# AnalogPair.net
KiCad netlist of a schematic drawn in EAGLE
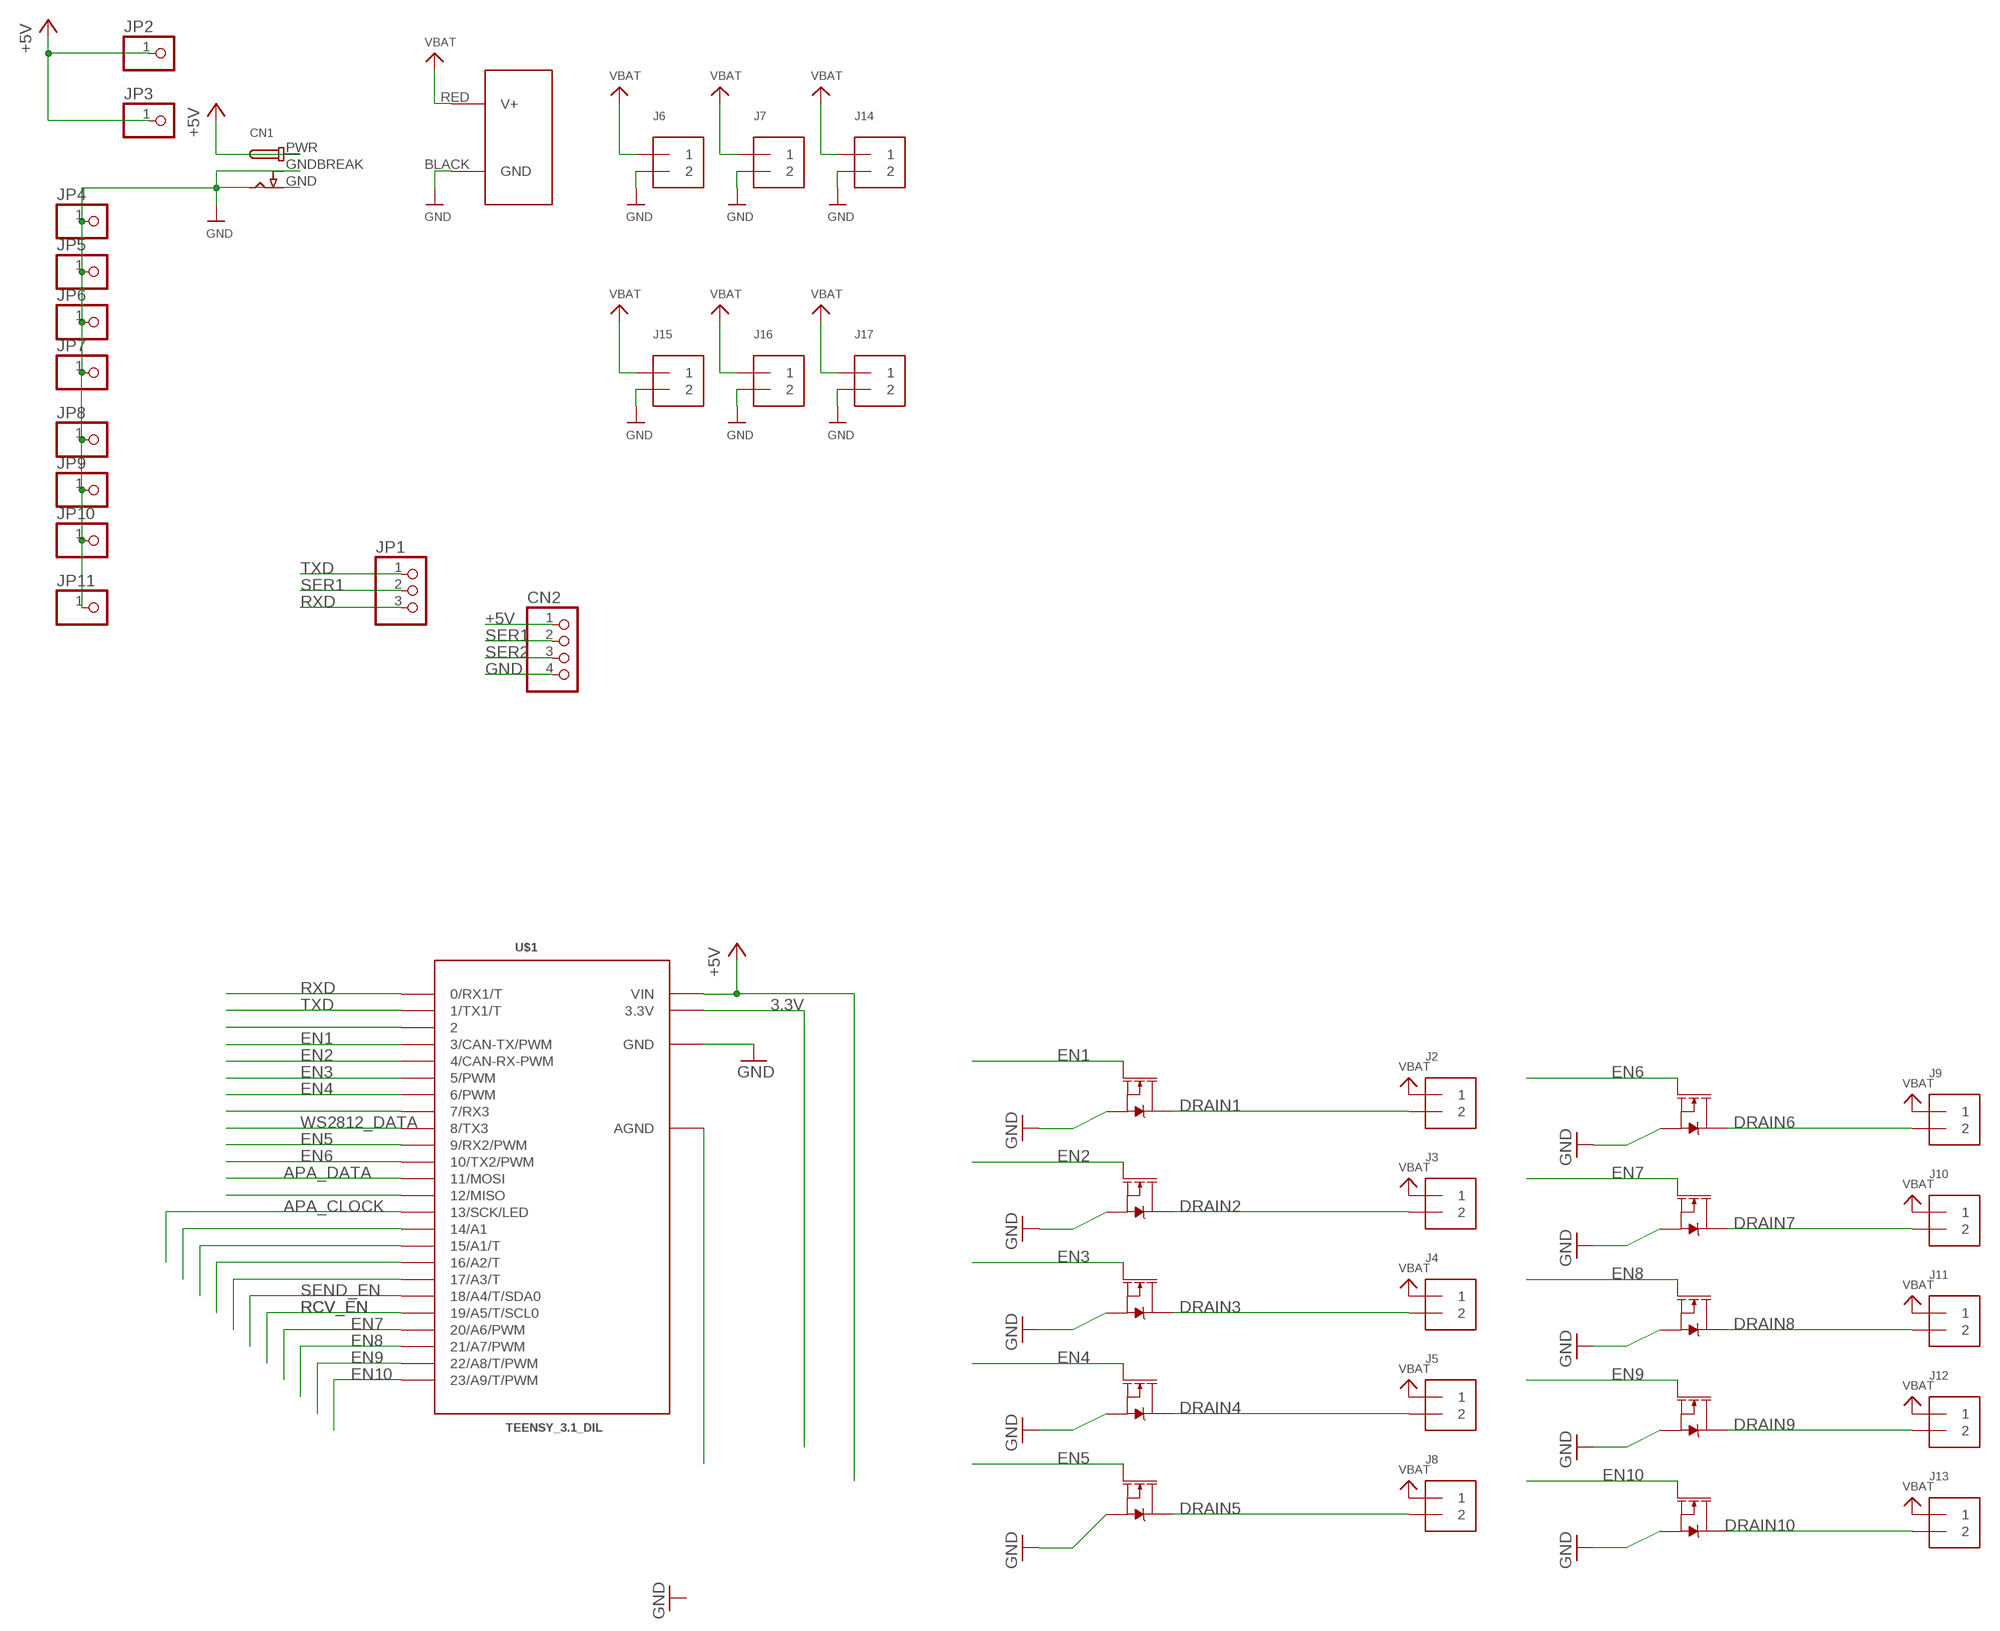
[diagram p0: schematic, sheet 1]

(export (version "E")
  (design (tool "Eeschema 10.0.6"))
  (components
    (comp (ref "CN1")
      (value "DCBARRELPTH")
      (footprint "eagle-import:DCJACK_2MM_PTH")
      (libsource (lib "eagle-import") (part "DCBARRELPTH"))
    )
    (comp (ref "CN2")
      (value "HEADER-1X4")
      (footprint "eagle-import:1X04_OVAL")
      (libsource (lib "eagle-import") (part "HEADER-1X4"))
    )
    (comp (ref "J1")
      (value "POWERPOLE_POWER25A")
      (footprint "eagle-import:POWERPOLE_PAIR_25A")
      (libsource (lib "eagle-import") (part "POWERPOLE_POWER25A"))
    )
    (comp (ref "J2")
      (value "TERMBLOCK_1X2")
      (footprint "eagle-import:TERMBLOCK_1X2-3.5MM")
      (libsource (lib "eagle-import") (part "TERMBLOCK_1X2"))
    )
    (comp (ref "J3")
      (value "TERMBLOCK_1X2")
      (footprint "eagle-import:TERMBLOCK_1X2-3.5MM")
      (libsource (lib "eagle-import") (part "TERMBLOCK_1X2"))
    )
    (comp (ref "J4")
      (value "TERMBLOCK_1X2")
      (footprint "eagle-import:TERMBLOCK_1X2-3.5MM")
      (libsource (lib "eagle-import") (part "TERMBLOCK_1X2"))
    )
    (comp (ref "J5")
      (value "TERMBLOCK_1X2")
      (footprint "eagle-import:TERMBLOCK_1X2-3.5MM")
      (libsource (lib "eagle-import") (part "TERMBLOCK_1X2"))
    )
    (comp (ref "J6")
      (value "TERMBLOCK_1X2")
      (footprint "eagle-import:TERMBLOCK_1X2-3.5MM")
      (libsource (lib "eagle-import") (part "TERMBLOCK_1X2"))
    )
    (comp (ref "J7")
      (value "TERMBLOCK_1X2")
      (footprint "eagle-import:TERMBLOCK_1X2-3.5MM")
      (libsource (lib "eagle-import") (part "TERMBLOCK_1X2"))
    )
    (comp (ref "J8")
      (value "TERMBLOCK_1X2")
      (footprint "eagle-import:TERMBLOCK_1X2-3.5MM")
      (libsource (lib "eagle-import") (part "TERMBLOCK_1X2"))
    )
    (comp (ref "J9")
      (value "TERMBLOCK_1X2")
      (footprint "eagle-import:TERMBLOCK_1X2-3.5MM")
      (libsource (lib "eagle-import") (part "TERMBLOCK_1X2"))
    )
    (comp (ref "J10")
      (value "TERMBLOCK_1X2")
      (footprint "eagle-import:TERMBLOCK_1X2-3.5MM")
      (libsource (lib "eagle-import") (part "TERMBLOCK_1X2"))
    )
    (comp (ref "J11")
      (value "TERMBLOCK_1X2")
      (footprint "eagle-import:TERMBLOCK_1X2-3.5MM")
      (libsource (lib "eagle-import") (part "TERMBLOCK_1X2"))
    )
    (comp (ref "J12")
      (value "TERMBLOCK_1X2")
      (footprint "eagle-import:TERMBLOCK_1X2-3.5MM")
      (libsource (lib "eagle-import") (part "TERMBLOCK_1X2"))
    )
    (comp (ref "J13")
      (value "TERMBLOCK_1X2")
      (footprint "eagle-import:TERMBLOCK_1X2-3.5MM")
      (libsource (lib "eagle-import") (part "TERMBLOCK_1X2"))
    )
    (comp (ref "J14")
      (value "TERMBLOCK_1X2")
      (footprint "eagle-import:TERMBLOCK_1X2-3.5MM")
      (libsource (lib "eagle-import") (part "TERMBLOCK_1X2"))
    )
    (comp (ref "J15")
      (value "TERMBLOCK_1X2")
      (footprint "eagle-import:TERMBLOCK_1X2-3.5MM")
      (libsource (lib "eagle-import") (part "TERMBLOCK_1X2"))
    )
    (comp (ref "J16")
      (value "TERMBLOCK_1X2")
      (footprint "eagle-import:TERMBLOCK_1X2-3.5MM")
      (libsource (lib "eagle-import") (part "TERMBLOCK_1X2"))
    )
    (comp (ref "J17")
      (value "TERMBLOCK_1X2")
      (footprint "eagle-import:TERMBLOCK_1X2-3.5MM")
      (libsource (lib "eagle-import") (part "TERMBLOCK_1X2"))
    )
    (comp (ref "JP1")
      (value "PINHD-1X3")
      (footprint "eagle-import:1X03")
      (libsource (lib "eagle-import") (part "PINHD-1X3"))
    )
    (comp (ref "JP2")
      (value "PINHD-1X1")
      (footprint "eagle-import:1X01")
      (libsource (lib "eagle-import") (part "PINHD-1X1"))
    )
    (comp (ref "JP3")
      (value "PINHD-1X1")
      (footprint "eagle-import:1X01")
      (libsource (lib "eagle-import") (part "PINHD-1X1"))
    )
    (comp (ref "JP4")
      (value "PINHD-1X1")
      (footprint "eagle-import:1X01")
      (libsource (lib "eagle-import") (part "PINHD-1X1"))
    )
    (comp (ref "JP5")
      (value "PINHD-1X1")
      (footprint "eagle-import:1X01")
      (libsource (lib "eagle-import") (part "PINHD-1X1"))
    )
    (comp (ref "JP6")
      (value "PINHD-1X1")
      (footprint "eagle-import:1X01")
      (libsource (lib "eagle-import") (part "PINHD-1X1"))
    )
    (comp (ref "JP7")
      (value "PINHD-1X1")
      (footprint "eagle-import:1X01")
      (libsource (lib "eagle-import") (part "PINHD-1X1"))
    )
    (comp (ref "JP8")
      (value "PINHD-1X1")
      (footprint "eagle-import:1X01")
      (libsource (lib "eagle-import") (part "PINHD-1X1"))
    )
    (comp (ref "JP9")
      (value "PINHD-1X1")
      (footprint "eagle-import:1X01")
      (libsource (lib "eagle-import") (part "PINHD-1X1"))
    )
    (comp (ref "JP10")
      (value "PINHD-1X1")
      (footprint "eagle-import:1X01")
      (libsource (lib "eagle-import") (part "PINHD-1X1"))
    )
    (comp (ref "JP11")
      (value "PINHD-1X1")
      (footprint "eagle-import:1X01")
      (libsource (lib "eagle-import") (part "PINHD-1X1"))
    )
    (comp (ref "Q1")
      (value "35A/25V/8.5mΩ")
      (footprint "eagle-import:DPAK")
      (libsource (lib "eagle-import") (part "MOSFET-NCH-FDD8780"))
    )
    (comp (ref "Q2")
      (value "35A/25V/8.5mΩ")
      (footprint "eagle-import:DPAK")
      (libsource (lib "eagle-import") (part "MOSFET-NCH-FDD8780"))
    )
    (comp (ref "Q3")
      (value "35A/25V/8.5mΩ")
      (footprint "eagle-import:DPAK")
      (libsource (lib "eagle-import") (part "MOSFET-NCH-FDD8780"))
    )
    (comp (ref "Q4")
      (value "35A/25V/8.5mΩ")
      (footprint "eagle-import:DPAK")
      (libsource (lib "eagle-import") (part "MOSFET-NCH-FDD8780"))
    )
    (comp (ref "Q5")
      (value "35A/25V/8.5mΩ")
      (footprint "eagle-import:DPAK")
      (libsource (lib "eagle-import") (part "MOSFET-NCH-FDD8780"))
    )
    (comp (ref "Q6")
      (value "35A/25V/8.5mΩ")
      (footprint "eagle-import:DPAK")
      (libsource (lib "eagle-import") (part "MOSFET-NCH-FDD8780"))
    )
    (comp (ref "Q7")
      (value "35A/25V/8.5mΩ")
      (footprint "eagle-import:DPAK")
      (libsource (lib "eagle-import") (part "MOSFET-NCH-FDD8780"))
    )
    (comp (ref "Q8")
      (value "35A/25V/8.5mΩ")
      (footprint "eagle-import:DPAK")
      (libsource (lib "eagle-import") (part "MOSFET-NCH-FDD8780"))
    )
    (comp (ref "Q9")
      (value "35A/25V/8.5mΩ")
      (footprint "eagle-import:DPAK")
      (libsource (lib "eagle-import") (part "MOSFET-NCH-FDD8780"))
    )
    (comp (ref "Q10")
      (value "35A/25V/8.5mΩ")
      (footprint "eagle-import:DPAK")
      (libsource (lib "eagle-import") (part "MOSFET-NCH-FDD8780"))
    )
    (comp (ref "U$1")
      (value "TEENSY_3.1_DIL")
      (footprint "eagle-import:TEENSY3-DIL")
      (libsource (lib "eagle-import") (part "TEENSY_3.1_DIL"))
    )
  )
  (nets
    (net (code "1") (name "+5V") (class "Default")
      (node (ref "CN1") (pin "PWR") (pinfunction "PWR_PWR") (pintype "power_in"))
      (node (ref "CN2") (pin "1") (pinfunction "1_1") (pintype "passive"))
      (node (ref "JP2") (pin "1") (pinfunction "1_1") (pintype "passive"))
      (node (ref "JP3") (pin "1") (pinfunction "1_1") (pintype "passive"))
      (node (ref "U$1") (pin "VIN") (pinfunction "VIN_VIN") (pintype "power_in"))
    )
    (net (code "2") (name "/3.3V") (class "Default")
      (node (ref "U$1") (pin "3.3V") (pinfunction "3.3V_3.3V") (pintype "power_in"))
    )
    (net (code "3") (name "/APA_CLOCK") (class "Default")
      (node (ref "U$1") (pin "13") (pinfunction "13/SCK/LED_13") (pintype "bidirectional"))
    )
    (net (code "4") (name "/APA_DATA") (class "Default")
      (node (ref "U$1") (pin "11") (pinfunction "11/MOSI_11") (pintype "bidirectional"))
    )
    (net (code "5") (name "/DRAIN1") (class "Default")
      (node (ref "J2") (pin "2") (pinfunction "2_2") (pintype "passive"))
      (node (ref "Q1") (pin "4") (pinfunction "D_4") (pintype "bidirectional"))
    )
    (net (code "6") (name "/DRAIN2") (class "Default")
      (node (ref "J3") (pin "2") (pinfunction "2_2") (pintype "passive"))
      (node (ref "Q3") (pin "4") (pinfunction "D_4") (pintype "bidirectional"))
    )
    (net (code "7") (name "/DRAIN3") (class "Default")
      (node (ref "J4") (pin "2") (pinfunction "2_2") (pintype "passive"))
      (node (ref "Q5") (pin "4") (pinfunction "D_4") (pintype "bidirectional"))
    )
    (net (code "8") (name "/DRAIN4") (class "Default")
      (node (ref "J5") (pin "2") (pinfunction "2_2") (pintype "passive"))
      (node (ref "Q6") (pin "4") (pinfunction "D_4") (pintype "bidirectional"))
    )
    (net (code "9") (name "/DRAIN5") (class "Default")
      (node (ref "J8") (pin "2") (pinfunction "2_2") (pintype "passive"))
      (node (ref "Q2") (pin "4") (pinfunction "D_4") (pintype "bidirectional"))
    )
    (net (code "10") (name "/DRAIN6") (class "Default")
      (node (ref "J9") (pin "2") (pinfunction "2_2") (pintype "passive"))
      (node (ref "Q4") (pin "4") (pinfunction "D_4") (pintype "bidirectional"))
    )
    (net (code "11") (name "/DRAIN7") (class "Default")
      (node (ref "J10") (pin "2") (pinfunction "2_2") (pintype "passive"))
      (node (ref "Q7") (pin "4") (pinfunction "D_4") (pintype "bidirectional"))
    )
    (net (code "12") (name "/DRAIN8") (class "Default")
      (node (ref "J11") (pin "2") (pinfunction "2_2") (pintype "passive"))
      (node (ref "Q8") (pin "4") (pinfunction "D_4") (pintype "bidirectional"))
    )
    (net (code "13") (name "/DRAIN9") (class "Default")
      (node (ref "J12") (pin "2") (pinfunction "2_2") (pintype "passive"))
      (node (ref "Q9") (pin "4") (pinfunction "D_4") (pintype "bidirectional"))
    )
    (net (code "14") (name "/DRAIN10") (class "Default")
      (node (ref "J13") (pin "2") (pinfunction "2_2") (pintype "passive"))
      (node (ref "Q10") (pin "4") (pinfunction "D_4") (pintype "bidirectional"))
    )
    (net (code "15") (name "/EN1") (class "Default")
      (node (ref "Q1") (pin "1") (pinfunction "G_1") (pintype "bidirectional"))
      (node (ref "U$1") (pin "3") (pinfunction "3/CAN-TX/PWM_3") (pintype "bidirectional"))
    )
    (net (code "16") (name "/EN2") (class "Default")
      (node (ref "Q3") (pin "1") (pinfunction "G_1") (pintype "bidirectional"))
      (node (ref "U$1") (pin "4") (pinfunction "4/CAN-RX-PWM_4") (pintype "bidirectional"))
    )
    (net (code "17") (name "/EN3") (class "Default")
      (node (ref "Q5") (pin "1") (pinfunction "G_1") (pintype "bidirectional"))
      (node (ref "U$1") (pin "5") (pinfunction "5/PWM_5") (pintype "bidirectional"))
    )
    (net (code "18") (name "/EN4") (class "Default")
      (node (ref "Q6") (pin "1") (pinfunction "G_1") (pintype "bidirectional"))
      (node (ref "U$1") (pin "6") (pinfunction "6/PWM_6") (pintype "bidirectional"))
    )
    (net (code "19") (name "/EN5") (class "Default")
      (node (ref "Q2") (pin "1") (pinfunction "G_1") (pintype "bidirectional"))
      (node (ref "U$1") (pin "9") (pinfunction "9/RX2/PWM_9") (pintype "bidirectional"))
    )
    (net (code "20") (name "/EN6") (class "Default")
      (node (ref "Q4") (pin "1") (pinfunction "G_1") (pintype "bidirectional"))
      (node (ref "U$1") (pin "10") (pinfunction "10/TX2/PWM_10") (pintype "bidirectional"))
    )
    (net (code "21") (name "/EN7") (class "Default")
      (node (ref "Q7") (pin "1") (pinfunction "G_1") (pintype "bidirectional"))
      (node (ref "U$1") (pin "20/A6") (pinfunction "20/A6/PWM_20/A6") (pintype "bidirectional"))
    )
    (net (code "22") (name "/EN8") (class "Default")
      (node (ref "Q8") (pin "1") (pinfunction "G_1") (pintype "bidirectional"))
      (node (ref "U$1") (pin "21/A7") (pinfunction "21/A7/PWM_21/A7") (pintype "bidirectional"))
    )
    (net (code "23") (name "/EN9") (class "Default")
      (node (ref "Q9") (pin "1") (pinfunction "G_1") (pintype "bidirectional"))
      (node (ref "U$1") (pin "22/A8") (pinfunction "22/A8/T/PWM_22/A8") (pintype "bidirectional"))
    )
    (net (code "24") (name "/EN10") (class "Default")
      (node (ref "Q10") (pin "1") (pinfunction "G_1") (pintype "bidirectional"))
      (node (ref "U$1") (pin "23/A9") (pinfunction "23/A9/T/PWM_23/A9") (pintype "bidirectional"))
    )
    (net (code "25") (name "/RCV_EN") (class "Default")
      (node (ref "U$1") (pin "19/A5") (pinfunction "19/A5/T/SCL0_19/A5") (pintype "bidirectional"))
    )
    (net (code "26") (name "/RXD") (class "Default")
      (node (ref "JP1") (pin "3") (pinfunction "3_3") (pintype "passive"))
      (node (ref "U$1") (pin "0") (pinfunction "0/RX1/T_0") (pintype "bidirectional"))
    )
    (net (code "27") (name "/SEND_EN") (class "Default")
      (node (ref "U$1") (pin "18/A4") (pinfunction "18/A4/T/SDA0_18/A4") (pintype "bidirectional"))
    )
    (net (code "28") (name "/SER1") (class "Default")
      (node (ref "CN2") (pin "2") (pinfunction "2_2") (pintype "passive"))
      (node (ref "JP1") (pin "2") (pinfunction "2_2") (pintype "passive"))
    )
    (net (code "29") (name "/SER2") (class "Default")
      (node (ref "CN2") (pin "3") (pinfunction "3_3") (pintype "passive"))
    )
    (net (code "30") (name "/TXD") (class "Default")
      (node (ref "JP1") (pin "1") (pinfunction "1_1") (pintype "passive"))
      (node (ref "U$1") (pin "1") (pinfunction "1/TX1/T_1") (pintype "bidirectional"))
    )
    (net (code "31") (name "/WS2812_DATA") (class "Default")
      (node (ref "U$1") (pin "8") (pinfunction "8/TX3_8") (pintype "bidirectional"))
    )
    (net (code "32") (name "GND") (class "Default")
      (node (ref "CN1") (pin "GND") (pinfunction "GND_GND") (pintype "power_in"))
      (node (ref "CN1") (pin "GNDBREAK") (pinfunction "GNDBREAK_GNDBREAK") (pintype "power_in"))
      (node (ref "CN2") (pin "4") (pinfunction "4_4") (pintype "passive"))
      (node (ref "J1") (pin "BLACK") (pinfunction "GND_BLACK") (pintype "power_in"))
      (node (ref "J14") (pin "2") (pinfunction "2_2") (pintype "passive"))
      (node (ref "J15") (pin "2") (pinfunction "2_2") (pintype "passive"))
      (node (ref "J16") (pin "2") (pinfunction "2_2") (pintype "passive"))
      (node (ref "J17") (pin "2") (pinfunction "2_2") (pintype "passive"))
      (node (ref "J6") (pin "2") (pinfunction "2_2") (pintype "passive"))
      (node (ref "J7") (pin "2") (pinfunction "2_2") (pintype "passive"))
      (node (ref "JP10") (pin "1") (pinfunction "1_1") (pintype "passive"))
      (node (ref "JP11") (pin "1") (pinfunction "1_1") (pintype "passive"))
      (node (ref "JP4") (pin "1") (pinfunction "1_1") (pintype "passive"))
      (node (ref "JP5") (pin "1") (pinfunction "1_1") (pintype "passive"))
      (node (ref "JP6") (pin "1") (pinfunction "1_1") (pintype "passive"))
      (node (ref "JP7") (pin "1") (pinfunction "1_1") (pintype "passive"))
      (node (ref "JP8") (pin "1") (pinfunction "1_1") (pintype "passive"))
      (node (ref "JP9") (pin "1") (pinfunction "1_1") (pintype "passive"))
      (node (ref "Q1") (pin "3") (pinfunction "S_3") (pintype "bidirectional"))
      (node (ref "Q10") (pin "3") (pinfunction "S_3") (pintype "bidirectional"))
      (node (ref "Q2") (pin "3") (pinfunction "S_3") (pintype "bidirectional"))
      (node (ref "Q3") (pin "3") (pinfunction "S_3") (pintype "bidirectional"))
      (node (ref "Q4") (pin "3") (pinfunction "S_3") (pintype "bidirectional"))
      (node (ref "Q5") (pin "3") (pinfunction "S_3") (pintype "bidirectional"))
      (node (ref "Q6") (pin "3") (pinfunction "S_3") (pintype "bidirectional"))
      (node (ref "Q7") (pin "3") (pinfunction "S_3") (pintype "bidirectional"))
      (node (ref "Q8") (pin "3") (pinfunction "S_3") (pintype "bidirectional"))
      (node (ref "Q9") (pin "3") (pinfunction "S_3") (pintype "bidirectional"))
      (node (ref "U$1") (pin "GND") (pinfunction "GND_GND") (pintype "power_in"))
    )
    (net (code "33") (name "VBAT") (class "Default")
      (node (ref "J1") (pin "RED") (pinfunction "V+_RED") (pintype "power_in"))
      (node (ref "J10") (pin "1") (pinfunction "1_1") (pintype "passive"))
      (node (ref "J11") (pin "1") (pinfunction "1_1") (pintype "passive"))
      (node (ref "J12") (pin "1") (pinfunction "1_1") (pintype "passive"))
      (node (ref "J13") (pin "1") (pinfunction "1_1") (pintype "passive"))
      (node (ref "J14") (pin "1") (pinfunction "1_1") (pintype "passive"))
      (node (ref "J15") (pin "1") (pinfunction "1_1") (pintype "passive"))
      (node (ref "J16") (pin "1") (pinfunction "1_1") (pintype "passive"))
      (node (ref "J17") (pin "1") (pinfunction "1_1") (pintype "passive"))
      (node (ref "J2") (pin "1") (pinfunction "1_1") (pintype "passive"))
      (node (ref "J3") (pin "1") (pinfunction "1_1") (pintype "passive"))
      (node (ref "J4") (pin "1") (pinfunction "1_1") (pintype "passive"))
      (node (ref "J5") (pin "1") (pinfunction "1_1") (pintype "passive"))
      (node (ref "J6") (pin "1") (pinfunction "1_1") (pintype "passive"))
      (node (ref "J7") (pin "1") (pinfunction "1_1") (pintype "passive"))
      (node (ref "J8") (pin "1") (pinfunction "1_1") (pintype "passive"))
      (node (ref "J9") (pin "1") (pinfunction "1_1") (pintype "passive"))
    )
    (net (code "34") (name "unconnected-(U$1-7{slash}RX3-Pad7)") (class "Default")
      (node (ref "U$1") (pin "7") (pinfunction "7/RX3_7") (pintype "bidirectional"))
    )
    (net (code "35") (name "unconnected-(U$1-12{slash}MISO-Pad12)") (class "Default")
      (node (ref "U$1") (pin "12") (pinfunction "12/MISO_12") (pintype "bidirectional"))
    )
    (net (code "36") (name "unconnected-(U$1-14{slash}A1-Pad14{slash}A0)") (class "Default")
      (node (ref "U$1") (pin "14/A0") (pinfunction "14/A1_14/A0") (pintype "bidirectional"))
    )
    (net (code "37") (name "unconnected-(U$1-15{slash}A1{slash}T-Pad15{slash}A1)") (class "Default")
      (node (ref "U$1") (pin "15/A1") (pinfunction "15/A1/T_15/A1") (pintype "bidirectional"))
    )
    (net (code "38") (name "unconnected-(U$1-16{slash}A2{slash}T-Pad16{slash}A2)") (class "Default")
      (node (ref "U$1") (pin "16/A2") (pinfunction "16/A2/T_16/A2") (pintype "bidirectional"))
    )
    (net (code "39") (name "unconnected-(U$1-17{slash}A3{slash}T-Pad17{slash}A3)") (class "Default")
      (node (ref "U$1") (pin "17/A3") (pinfunction "17/A3/T_17/A3") (pintype "bidirectional"))
    )
    (net (code "40") (name "unconnected-(U$1-Pad2)") (class "Default")
      (node (ref "U$1") (pin "2") (pinfunction "2_2") (pintype "bidirectional"))
    )
    (net (code "41") (name "unconnected-(U$1-PadAGND)") (class "Default")
      (node (ref "U$1") (pin "AGND") (pinfunction "AGND_AGND") (pintype "power_in"))
    )
  )
)
